# R001X.net
KiCad netlist of a schematic drawn in EAGLE
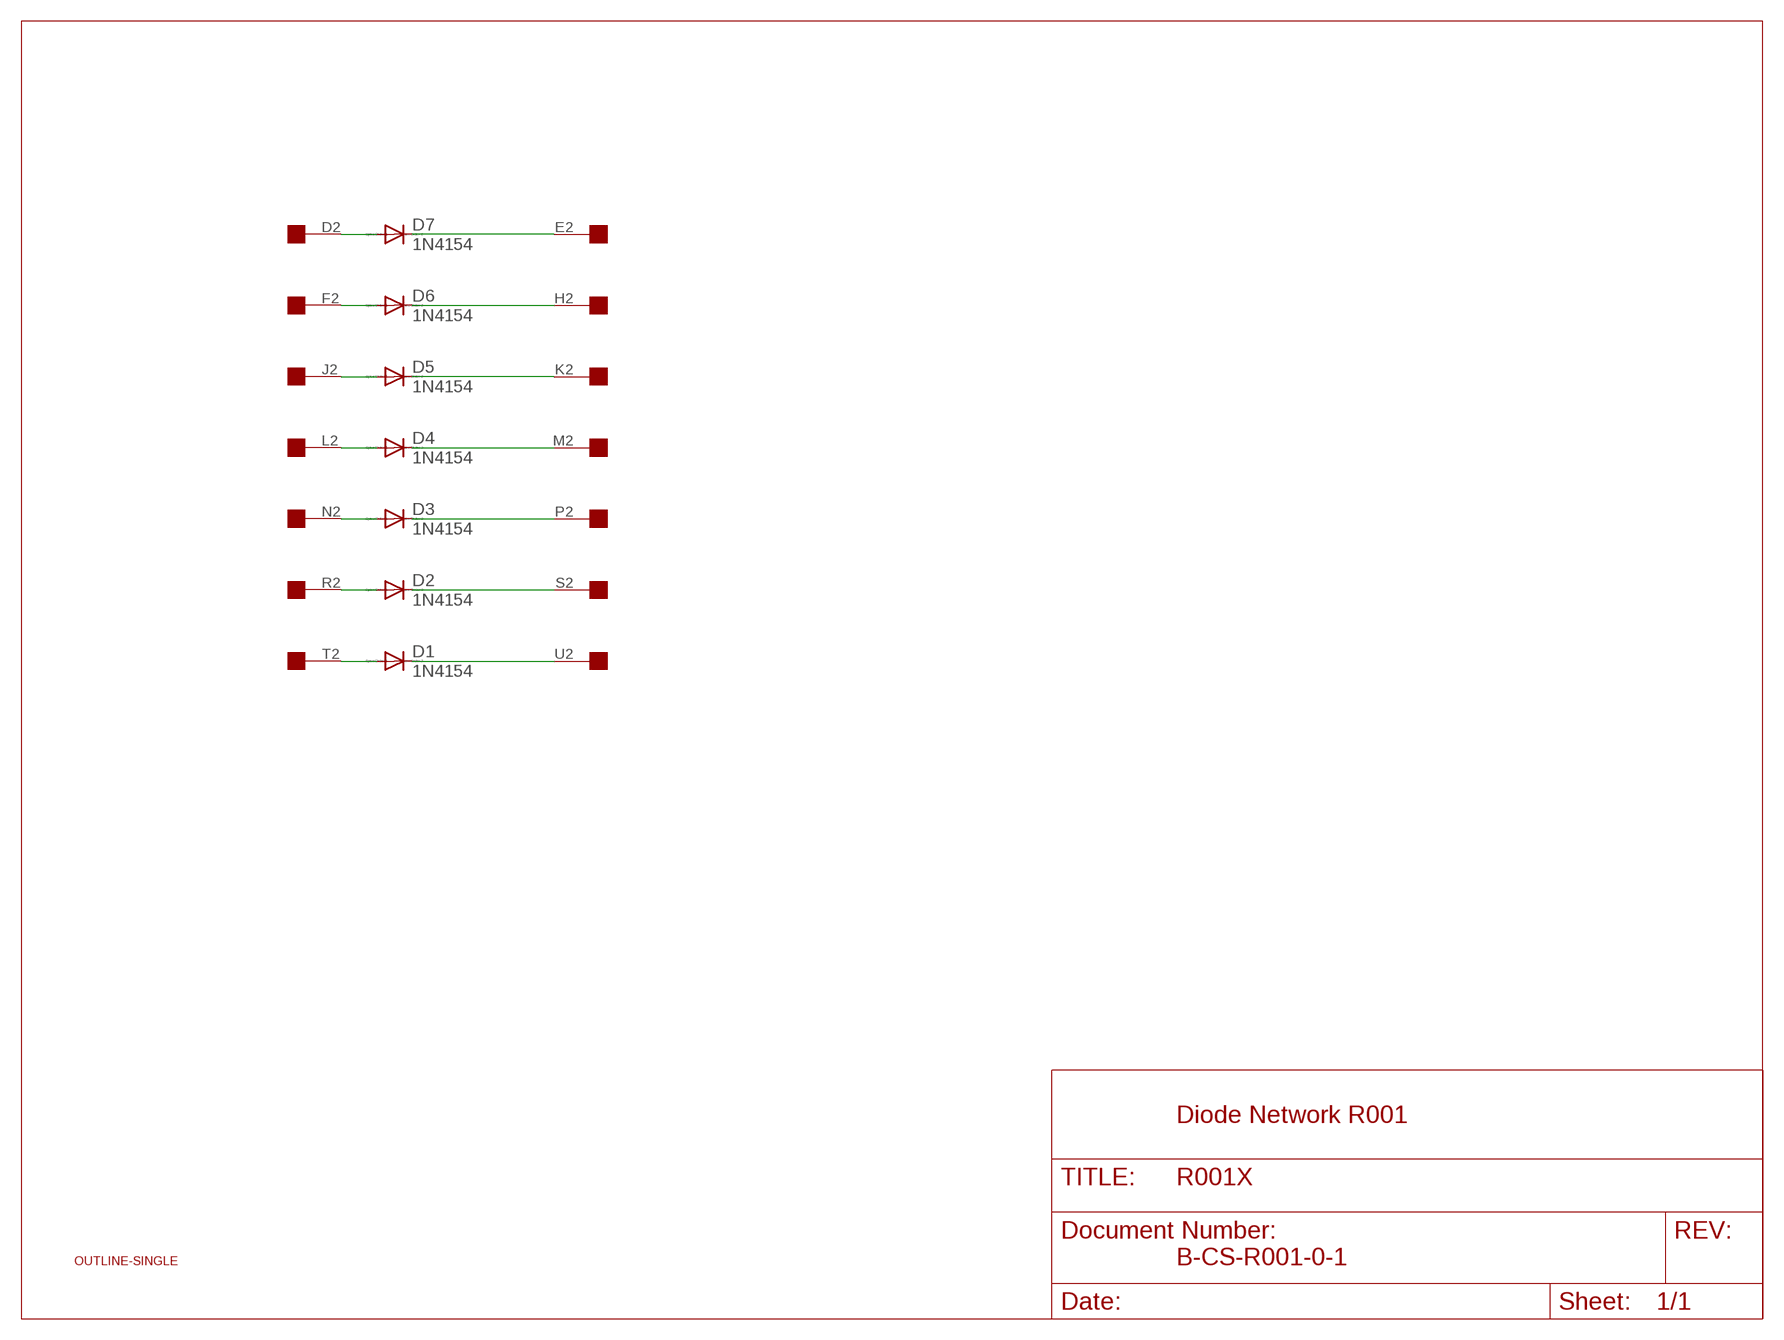
[diagram p0: schematic, sheet 1]

(export (version "E")
  (design (tool "Eeschema 10.0.6"))
  (components
    (comp (ref "D1")
      (value "1N4154")
      (footprint "eagle-import:DO35-10")
      (libsource (lib "eagle-import") (part "1N4148DO35-10"))
    )
    (comp (ref "D2")
      (value "1N4154")
      (footprint "eagle-import:DO35-10")
      (libsource (lib "eagle-import") (part "1N4148DO35-10"))
    )
    (comp (ref "D3")
      (value "1N4154")
      (footprint "eagle-import:DO35-10")
      (libsource (lib "eagle-import") (part "1N4148DO35-10"))
    )
    (comp (ref "D4")
      (value "1N4154")
      (footprint "eagle-import:DO35-10")
      (libsource (lib "eagle-import") (part "1N4148DO35-10"))
    )
    (comp (ref "D5")
      (value "1N4154")
      (footprint "eagle-import:DO35-10")
      (libsource (lib "eagle-import") (part "1N4148DO35-10"))
    )
    (comp (ref "D6")
      (value "1N4154")
      (footprint "eagle-import:DO35-10")
      (libsource (lib "eagle-import") (part "1N4148DO35-10"))
    )
    (comp (ref "D7")
      (value "1N4154")
      (footprint "eagle-import:DO35-10")
      (libsource (lib "eagle-import") (part "1N4148DO35-10"))
    )
    (comp (ref "U$1")
      (value "OUTLINE-SINGLE")
      (footprint "eagle-import:SINGLE")
      (libsource (lib "eagle-import") (part "OUTLINE-SINGLE"))
    )
    (comp (ref "U$2")
      (value "EDGE-1")
      (footprint "eagle-import:EDGE-CON1")
      (libsource (lib "eagle-import") (part "EDGE-1"))
    )
  )
  (nets
    (net (code "1") (name "Net-(U$2D-1)") (class "Default")
      (node (ref "D7") (pin "A") (pinfunction "A_A") (pintype "passive"))
      (node (ref "U$2") (pin "D2") (pinfunction "1_D2") (pintype "bidirectional"))
    )
    (net (code "2") (name "Net-(U$2E-1)") (class "Default")
      (node (ref "D7") (pin "C") (pinfunction "C_C") (pintype "passive"))
      (node (ref "U$2") (pin "E2") (pinfunction "1_E2") (pintype "bidirectional"))
    )
    (net (code "3") (name "Net-(U$2F-1)") (class "Default")
      (node (ref "D6") (pin "A") (pinfunction "A_A") (pintype "passive"))
      (node (ref "U$2") (pin "F2") (pinfunction "1_F2") (pintype "bidirectional"))
    )
    (net (code "4") (name "Net-(U$2G-1)") (class "Default")
      (node (ref "D6") (pin "C") (pinfunction "C_C") (pintype "passive"))
      (node (ref "U$2") (pin "H2") (pinfunction "1_H2") (pintype "bidirectional"))
    )
    (net (code "5") (name "Net-(U$2H-1)") (class "Default")
      (node (ref "D5") (pin "A") (pinfunction "A_A") (pintype "passive"))
      (node (ref "U$2") (pin "J2") (pinfunction "1_J2") (pintype "bidirectional"))
    )
    (net (code "6") (name "Net-(U$2I-1)") (class "Default")
      (node (ref "D5") (pin "C") (pinfunction "C_C") (pintype "passive"))
      (node (ref "U$2") (pin "K2") (pinfunction "1_K2") (pintype "bidirectional"))
    )
    (net (code "7") (name "Net-(U$2J-1)") (class "Default")
      (node (ref "D4") (pin "A") (pinfunction "A_A") (pintype "passive"))
      (node (ref "U$2") (pin "L2") (pinfunction "1_L2") (pintype "bidirectional"))
    )
    (net (code "8") (name "Net-(U$2K-1)") (class "Default")
      (node (ref "D4") (pin "C") (pinfunction "C_C") (pintype "passive"))
      (node (ref "U$2") (pin "M2") (pinfunction "1_M2") (pintype "bidirectional"))
    )
    (net (code "9") (name "Net-(U$2L-1)") (class "Default")
      (node (ref "D3") (pin "A") (pinfunction "A_A") (pintype "passive"))
      (node (ref "U$2") (pin "N2") (pinfunction "1_N2") (pintype "bidirectional"))
    )
    (net (code "10") (name "Net-(U$2M-1)") (class "Default")
      (node (ref "D3") (pin "C") (pinfunction "C_C") (pintype "passive"))
      (node (ref "U$2") (pin "P2") (pinfunction "1_P2") (pintype "bidirectional"))
    )
    (net (code "11") (name "Net-(U$2N-1)") (class "Default")
      (node (ref "D2") (pin "A") (pinfunction "A_A") (pintype "passive"))
      (node (ref "U$2") (pin "R2") (pinfunction "1_R2") (pintype "bidirectional"))
    )
    (net (code "12") (name "Net-(U$2O-1)") (class "Default")
      (node (ref "D2") (pin "C") (pinfunction "C_C") (pintype "passive"))
      (node (ref "U$2") (pin "S2") (pinfunction "1_S2") (pintype "bidirectional"))
    )
    (net (code "13") (name "Net-(U$2P-1)") (class "Default")
      (node (ref "D1") (pin "A") (pinfunction "A_A") (pintype "passive"))
      (node (ref "U$2") (pin "T2") (pinfunction "1_T2") (pintype "bidirectional"))
    )
    (net (code "14") (name "Net-(U$2Q-1)") (class "Default")
      (node (ref "D1") (pin "C") (pinfunction "C_C") (pintype "passive"))
      (node (ref "U$2") (pin "U2") (pinfunction "1_U2") (pintype "bidirectional"))
    )
  )
)
